# Esquem_tico.net
KiCad netlist of a schematic drawn in Altium Designer
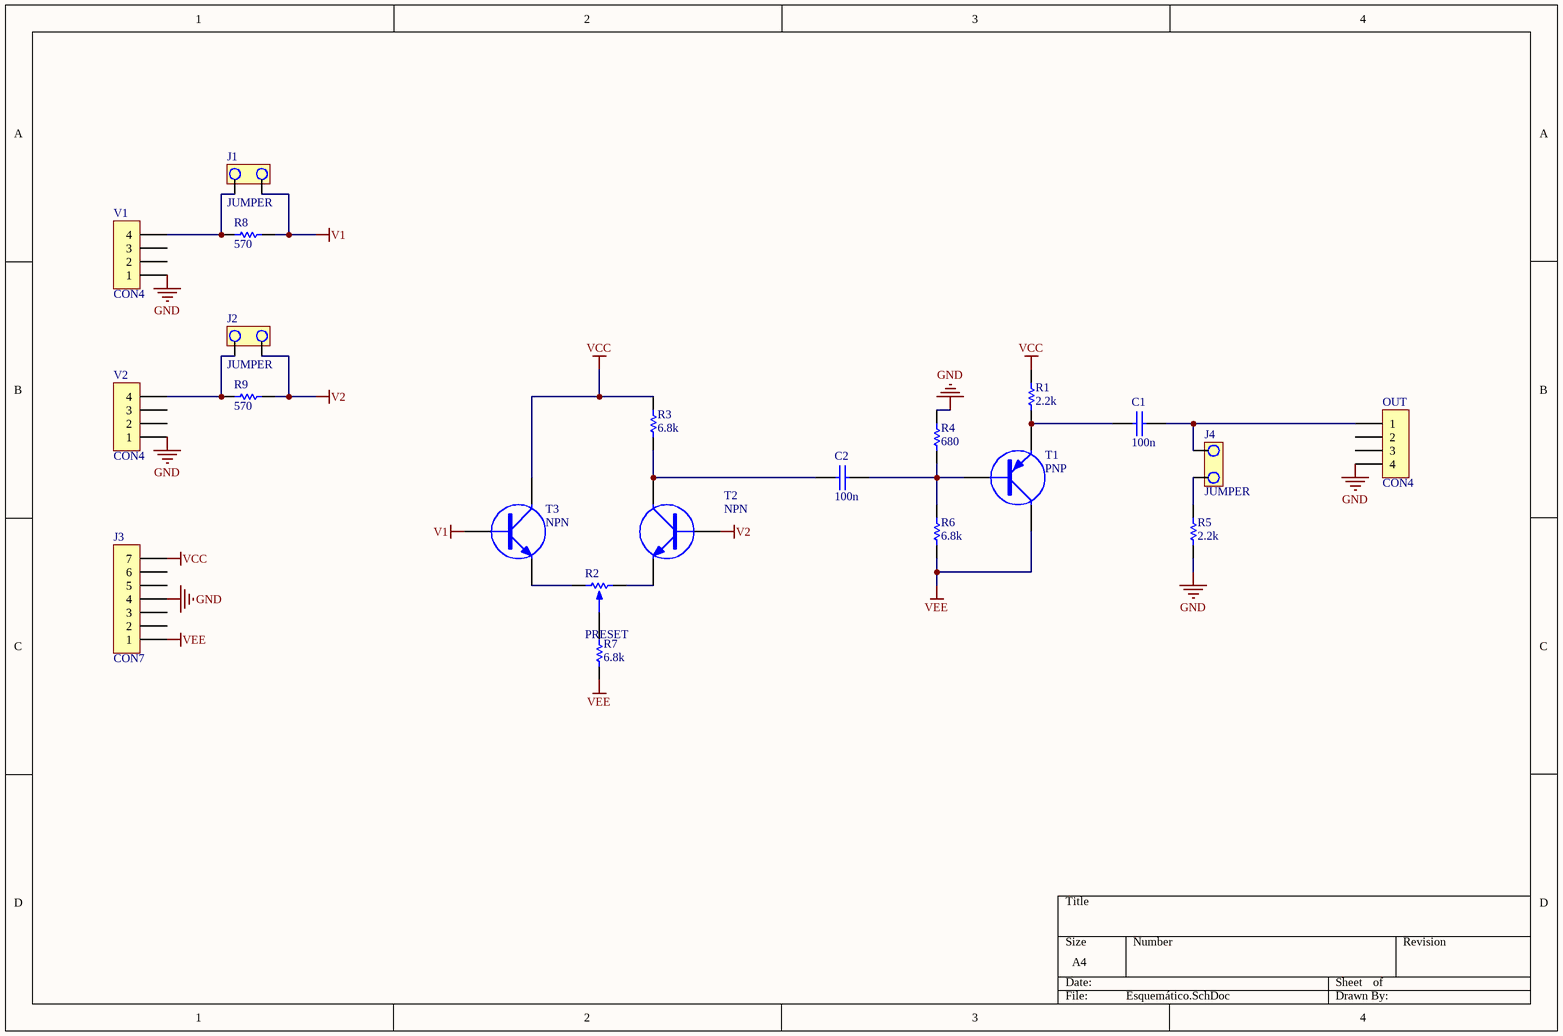
[diagram p0: Esquemático.SchDoc]

(export (version "E")
  (design (tool "Eeschema 10.0.6"))
  (components
    (comp (ref "C1") (value "100n") (footprint "CAP200") (libsource (lib "LIBEBAL") (part "CAP")))
    (comp (ref "C2") (value "100n") (footprint "CAP200") (libsource (lib "LIBEBAL") (part "CAP")))
    (comp (ref "J1") (value "JUMPER") (footprint "JUMPER2") (libsource (lib "") (part "JUMPER_1")))
    (comp (ref "J2") (value "JUMPER") (footprint "JUMPER2") (libsource (lib "") (part "JUMPER_1")))
    (comp (ref "J3") (value "CON7") (footprint "SIP7") (libsource (lib "LIBEBAL") (part "CON7")))
    (comp (ref "J4") (value "JUMPER") (footprint "JUMPER2") (libsource (lib "LIBEBAL") (part "JUMPER")))
    (comp (ref "OUT") (value "CON4") (footprint "SIP4") (libsource (lib "") (part "CON4_1")))
    (comp (ref "R1") (value "2.2k") (footprint "RES400") (libsource (lib "LIBEBAL") (part "RES")))
    (comp (ref "R2") (value "PRESET") (footprint "PRESET V") (libsource (lib "LIBEBAL") (part "PRESET")))
    (comp (ref "R3") (value "6.8k") (footprint "RES400") (libsource (lib "LIBEBAL") (part "RES")))
    (comp (ref "R4") (value "680") (footprint "RES400") (libsource (lib "LIBEBAL") (part "RES")))
    (comp (ref "R5") (value "2.2k") (footprint "RES400") (libsource (lib "LIBEBAL") (part "RES")))
    (comp (ref "R6") (value "6.8k") (footprint "RES400") (libsource (lib "LIBEBAL") (part "RES")))
    (comp (ref "R7") (value "6.8k") (footprint "RES400") (libsource (lib "LIBEBAL") (part "RES")))
    (comp (ref "R8") (value "570") (footprint "RES400") (libsource (lib "LIBEBAL") (part "RES")))
    (comp (ref "R9") (value "570") (footprint "RES400") (libsource (lib "LIBEBAL") (part "RES")))
    (comp (ref "T1") (value "PNP") (footprint "TO92") (libsource (lib "LIBEBAL") (part "TRANSISTOR PNP")))
    (comp (ref "T2") (value "NPN") (footprint "TO92") (libsource (lib "LIBEBAL") (part "TRANSISTOR NPN")))
    (comp (ref "T3") (value "NPN") (footprint "TO92") (libsource (lib "LIBEBAL") (part "TRANSISTOR NPN")))
    (comp (ref "V1") (value "CON4") (footprint "SIP4") (libsource (lib "LIBEBAL") (part "CON4")))
    (comp (ref "V2") (value "CON4") (footprint "SIP4") (libsource (lib "LIBEBAL") (part "CON4")))
  )
  (nets
    (net (code "1") (name "GND") (class "Default")
      (node (ref "J3") (pin "4") (pinfunction "4_4") (pintype "passive"))
      (node (ref "OUT") (pin "4") (pinfunction "4_4") (pintype "passive"))
      (node (ref "R4") (pin "2") (pinfunction "2_2") (pintype "passive"))
      (node (ref "R5") (pin "1") (pinfunction "1_1") (pintype "passive"))
      (node (ref "V1") (pin "1") (pinfunction "1_1") (pintype "passive"))
      (node (ref "V2") (pin "1") (pinfunction "1_1") (pintype "passive"))
    )
    (net (code "2") (name "Net-(C1-Pad2)") (class "Default")
      (node (ref "C1") (pin "2") (pinfunction "2_2") (pintype "passive"))
      (node (ref "J4") (pin "2") (pinfunction "2_2") (pintype "passive"))
      (node (ref "OUT") (pin "1") (pinfunction "1_1") (pintype "passive"))
    )
    (net (code "3") (name "Net-(J1-Pad2)") (class "Default")
      (node (ref "J1") (pin "2") (pinfunction "2_2") (pintype "passive"))
      (node (ref "R8") (pin "1") (pinfunction "1_1") (pintype "passive"))
      (node (ref "V1") (pin "4") (pinfunction "4_4") (pintype "passive"))
    )
    (net (code "4") (name "Net-(J2-Pad2)") (class "Default")
      (node (ref "J2") (pin "2") (pinfunction "2_2") (pintype "passive"))
      (node (ref "R9") (pin "1") (pinfunction "1_1") (pintype "passive"))
      (node (ref "V2") (pin "4") (pinfunction "4_4") (pintype "passive"))
    )
    (net (code "5") (name "Net-(J4-Pad1)") (class "Default")
      (node (ref "J4") (pin "1") (pinfunction "1_1") (pintype "passive"))
      (node (ref "R5") (pin "2") (pinfunction "2_2") (pintype "passive"))
    )
    (net (code "6") (name "Net-(R2-Pad2)") (class "Default")
      (node (ref "R2") (pin "2") (pinfunction "2_2") (pintype "passive"))
      (node (ref "R7") (pin "2") (pinfunction "2_2") (pintype "passive"))
    )
    (net (code "7") (name "Net-(T1-B)") (class "Default")
      (node (ref "C2") (pin "2") (pinfunction "2_2") (pintype "passive"))
      (node (ref "R4") (pin "1") (pinfunction "1_1") (pintype "passive"))
      (node (ref "R6") (pin "2") (pinfunction "2_2") (pintype "passive"))
      (node (ref "T1") (pin "1") (pinfunction "B_1") (pintype "passive"))
    )
    (net (code "8") (name "Net-(T1-E)") (class "Default")
      (node (ref "C1") (pin "1") (pinfunction "1_1") (pintype "passive"))
      (node (ref "R1") (pin "1") (pinfunction "1_1") (pintype "passive"))
      (node (ref "T1") (pin "3") (pinfunction "E_3") (pintype "passive"))
    )
    (net (code "9") (name "Net-(T2-C)") (class "Default")
      (node (ref "C2") (pin "1") (pinfunction "1_1") (pintype "passive"))
      (node (ref "R3") (pin "1") (pinfunction "1_1") (pintype "passive"))
      (node (ref "T2") (pin "2") (pinfunction "C_2") (pintype "passive"))
    )
    (net (code "10") (name "Net-(T2-E)") (class "Default")
      (node (ref "R2") (pin "1") (pinfunction "1_1") (pintype "passive"))
      (node (ref "T2") (pin "3") (pinfunction "E_3") (pintype "passive"))
    )
    (net (code "11") (name "Net-(T3-E)") (class "Default")
      (node (ref "R2") (pin "3") (pinfunction "3_3") (pintype "passive"))
      (node (ref "T3") (pin "3") (pinfunction "E_3") (pintype "passive"))
    )
    (net (code "12") (name "V1") (class "Default")
      (node (ref "J1") (pin "1") (pinfunction "1_1") (pintype "passive"))
      (node (ref "R8") (pin "2") (pinfunction "2_2") (pintype "passive"))
      (node (ref "T3") (pin "1") (pinfunction "B_1") (pintype "passive"))
    )
    (net (code "13") (name "V2") (class "Default")
      (node (ref "J2") (pin "1") (pinfunction "1_1") (pintype "passive"))
      (node (ref "R9") (pin "2") (pinfunction "2_2") (pintype "passive"))
      (node (ref "T2") (pin "1") (pinfunction "B_1") (pintype "passive"))
    )
    (net (code "14") (name "VCC") (class "Default")
      (node (ref "J3") (pin "7") (pinfunction "7_7") (pintype "passive"))
      (node (ref "R1") (pin "2") (pinfunction "2_2") (pintype "passive"))
      (node (ref "R3") (pin "2") (pinfunction "2_2") (pintype "passive"))
      (node (ref "T3") (pin "2") (pinfunction "C_2") (pintype "passive"))
    )
    (net (code "15") (name "VEE") (class "Default")
      (node (ref "J3") (pin "1") (pinfunction "1_1") (pintype "passive"))
      (node (ref "R6") (pin "1") (pinfunction "1_1") (pintype "passive"))
      (node (ref "R7") (pin "1") (pinfunction "1_1") (pintype "passive"))
      (node (ref "T1") (pin "2") (pinfunction "C_2") (pintype "passive"))
    )
    (net (code "16") (name "unconnected-(J3-Pad2)") (class "Default")
      (node (ref "J3") (pin "2") (pinfunction "2_2") (pintype "passive"))
    )
    (net (code "17") (name "unconnected-(J3-Pad3)") (class "Default")
      (node (ref "J3") (pin "3") (pinfunction "3_3") (pintype "passive"))
    )
    (net (code "18") (name "unconnected-(J3-Pad5)") (class "Default")
      (node (ref "J3") (pin "5") (pinfunction "5_5") (pintype "passive"))
    )
    (net (code "19") (name "unconnected-(J3-Pad6)") (class "Default")
      (node (ref "J3") (pin "6") (pinfunction "6_6") (pintype "passive"))
    )
    (net (code "20") (name "unconnected-(OUT-Pad2)") (class "Default")
      (node (ref "OUT") (pin "2") (pinfunction "2_2") (pintype "passive"))
    )
    (net (code "21") (name "unconnected-(OUT-Pad3)") (class "Default")
      (node (ref "OUT") (pin "3") (pinfunction "3_3") (pintype "passive"))
    )
    (net (code "22") (name "unconnected-(V1-Pad2)") (class "Default")
      (node (ref "V1") (pin "2") (pinfunction "2_2") (pintype "passive"))
    )
    (net (code "23") (name "unconnected-(V1-Pad3)") (class "Default")
      (node (ref "V1") (pin "3") (pinfunction "3_3") (pintype "passive"))
    )
    (net (code "24") (name "unconnected-(V2-Pad2)") (class "Default")
      (node (ref "V2") (pin "2") (pinfunction "2_2") (pintype "passive"))
    )
    (net (code "25") (name "unconnected-(V2-Pad3)") (class "Default")
      (node (ref "V2") (pin "3") (pinfunction "3_3") (pintype "passive"))
    )
  )
)
